# xmas_tree_pcb_A.net
KiCad netlist of a schematic drawn in EAGLE
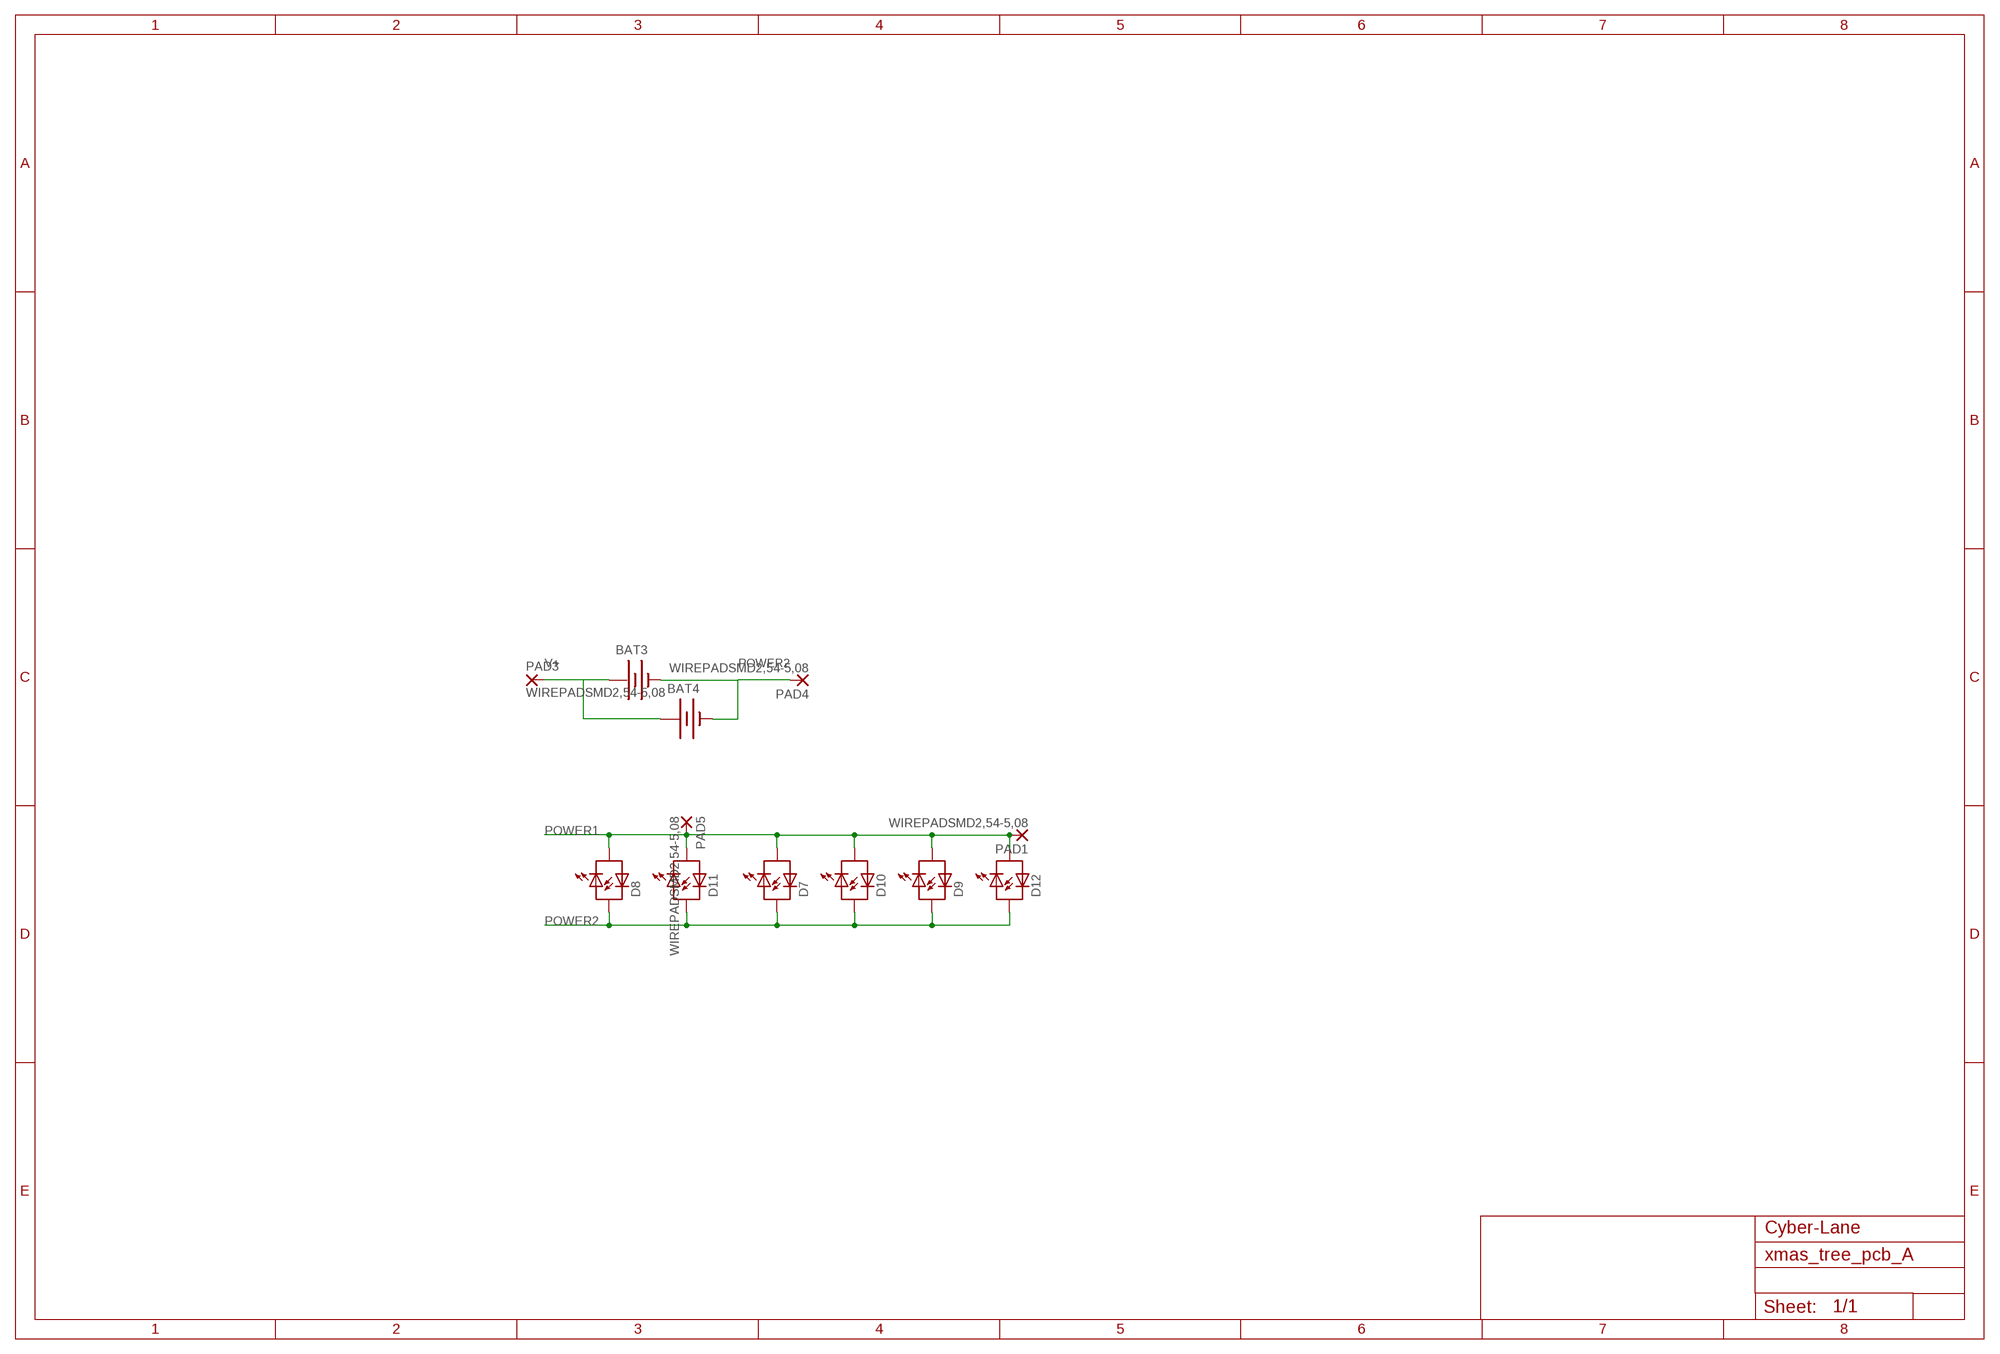
[diagram p0: schematic, sheet 1]

(export (version "E")
  (design (tool "Eeschema 10.0.6"))
  (components
    (comp (ref "BAT3")
      (value "BATTERY20PTH")
      (footprint "eagle-import:BATTCOM_20MM_PTH")
      (libsource (lib "eagle-import") (part "BATTERY20PTH"))
    )
    (comp (ref "BAT4")
      (value "BATTERY20PTH")
      (footprint "eagle-import:BATTCOM_20MM_PTH")
      (libsource (lib "eagle-import") (part "BATTERY20PTH"))
    )
    (comp (ref "D7")
      (value "LED_BI_COLOR")
      (footprint "eagle-import:LED3MM")
      (libsource (lib "eagle-import") (part "LED_BI_COLOR"))
    )
    (comp (ref "D8")
      (value "LED_BI_COLOR")
      (footprint "eagle-import:LED3MM")
      (libsource (lib "eagle-import") (part "LED_BI_COLOR"))
    )
    (comp (ref "D9")
      (value "LED_BI_COLOR")
      (footprint "eagle-import:LED3MM")
      (libsource (lib "eagle-import") (part "LED_BI_COLOR"))
    )
    (comp (ref "D10")
      (value "LED_BI_COLOR")
      (footprint "eagle-import:LED3MM")
      (libsource (lib "eagle-import") (part "LED_BI_COLOR"))
    )
    (comp (ref "D11")
      (value "LED_BI_COLOR")
      (footprint "eagle-import:LED3MM")
      (libsource (lib "eagle-import") (part "LED_BI_COLOR"))
    )
    (comp (ref "D12")
      (value "LED_BI_COLOR")
      (footprint "eagle-import:LED3MM")
      (libsource (lib "eagle-import") (part "LED_BI_COLOR"))
    )
    (comp (ref "PAD1")
      (value "WIREPADSMD2,54-5,08")
      (footprint "eagle-import:SMD2,54-5,08")
      (libsource (lib "eagle-import") (part "WIREPADSMD2,54-5,08"))
    )
    (comp (ref "PAD3")
      (value "WIREPADSMD2,54-5,08")
      (footprint "eagle-import:SMD2,54-5,08")
      (libsource (lib "eagle-import") (part "WIREPADSMD2,54-5,08"))
    )
    (comp (ref "PAD4")
      (value "WIREPADSMD2,54-5,08")
      (footprint "eagle-import:SMD2,54-5,08")
      (libsource (lib "eagle-import") (part "WIREPADSMD2,54-5,08"))
    )
    (comp (ref "PAD5")
      (value "WIREPADSMD2,54-5,08")
      (footprint "eagle-import:SMD2,54-5,08")
      (libsource (lib "eagle-import") (part "WIREPADSMD2,54-5,08"))
    )
  )
  (nets
    (net (code "1") (name "/POWER1") (class "Default")
      (node (ref "D10") (pin "K") (pinfunction "C1_K") (pintype "passive"))
      (node (ref "D11") (pin "K") (pinfunction "C1_K") (pintype "passive"))
      (node (ref "D12") (pin "K") (pinfunction "C1_K") (pintype "passive"))
      (node (ref "D7") (pin "K") (pinfunction "C1_K") (pintype "passive"))
      (node (ref "D8") (pin "K") (pinfunction "C1_K") (pintype "passive"))
      (node (ref "D9") (pin "K") (pinfunction "C1_K") (pintype "passive"))
      (node (ref "PAD1") (pin "1") (pinfunction "P_1") (pintype "passive"))
      (node (ref "PAD5") (pin "1") (pinfunction "P_1") (pintype "passive"))
    )
    (net (code "2") (name "/POWER2") (class "Default")
      (node (ref "BAT3") (pin "2") (pinfunction "-_2") (pintype "power_in"))
      (node (ref "BAT4") (pin "2") (pinfunction "-_2") (pintype "power_in"))
      (node (ref "D10") (pin "A") (pinfunction "A1_A") (pintype "passive"))
      (node (ref "D11") (pin "A") (pinfunction "A1_A") (pintype "passive"))
      (node (ref "D12") (pin "A") (pinfunction "A1_A") (pintype "passive"))
      (node (ref "D7") (pin "A") (pinfunction "A1_A") (pintype "passive"))
      (node (ref "D8") (pin "A") (pinfunction "A1_A") (pintype "passive"))
      (node (ref "D9") (pin "A") (pinfunction "A1_A") (pintype "passive"))
      (node (ref "PAD4") (pin "1") (pinfunction "P_1") (pintype "passive"))
    )
    (net (code "3") (name "/V+") (class "Default")
      (node (ref "BAT3") (pin "1") (pinfunction "+_1") (pintype "power_in"))
      (node (ref "BAT4") (pin "1") (pinfunction "+_1") (pintype "power_in"))
      (node (ref "PAD3") (pin "1") (pinfunction "P_1") (pintype "passive"))
    )
  )
)
